# main_stack_dual_channel.net
KiCad netlist of a schematic drawn in Altium Designer
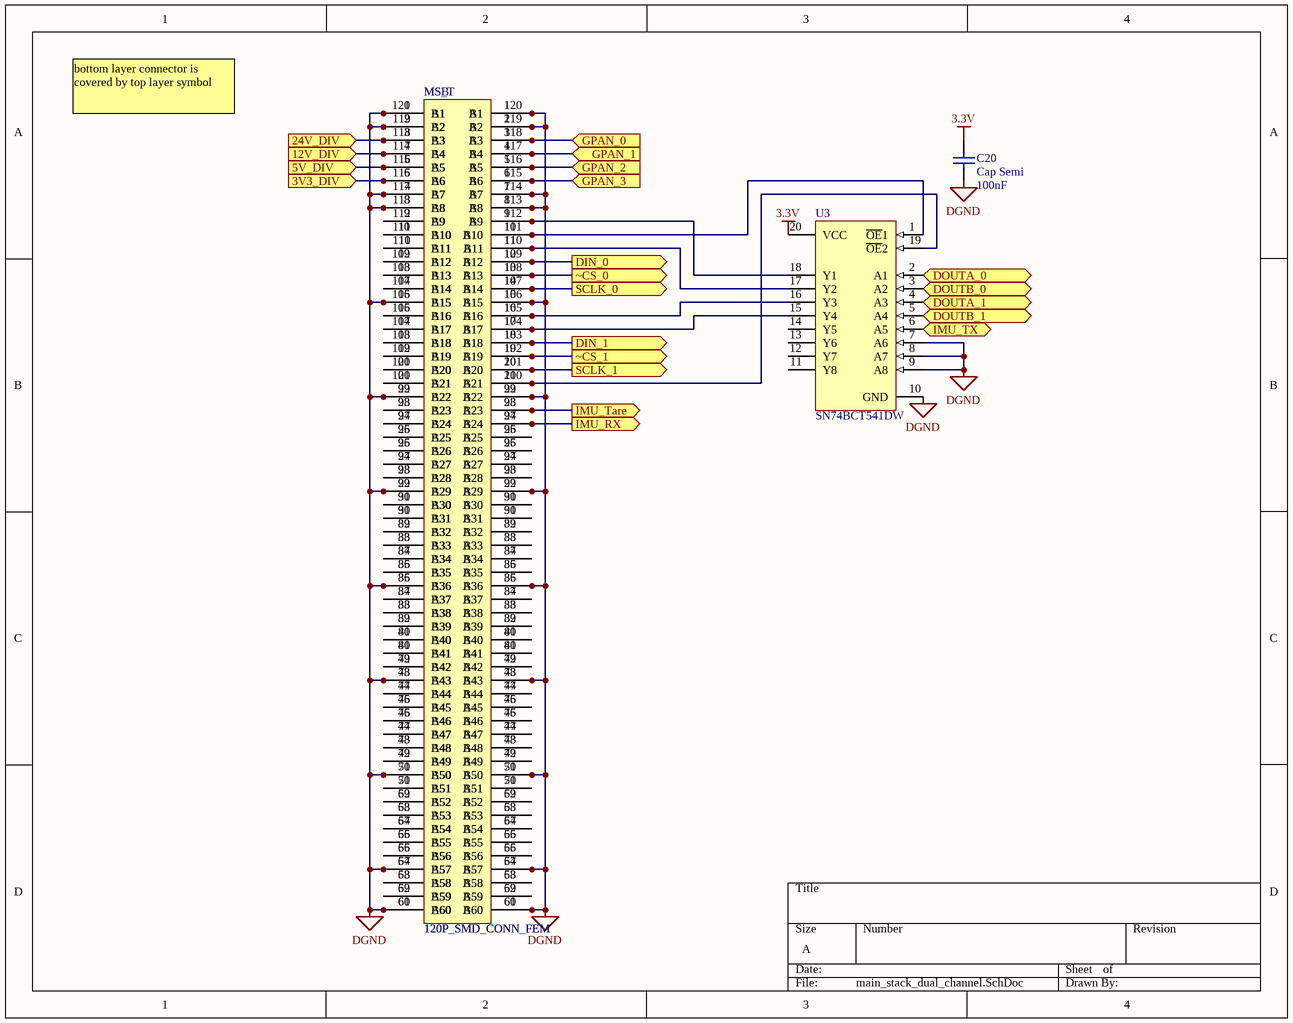
[diagram p0: main_stack_dual_channel.SchDoc]

(export (version "E")
  (design (tool "Eeschema 10.0.6"))
  (components
    (comp (ref "C20")
      (value "Cap Semi")
      (footprint "C0805")
      (description "Capacitor (Semiconductor SIM Model)")
      (fields (field (name "ALTIUM_VALUE") "100nF") (field (name "PUBLISHER") "Altium Limited"))
      (libsource (lib "Miscellaneous Devices") (part "Cap Semi"))
    )
    (comp (ref "MSB")
      (value "120P_SMD_CONN_FEM")
      (footprint "FX2-120P-1.27SV")
      (description "Main Stack Connector, Female")
      (fields (field (name "PART NUMBER") "FX2-120P-1.27SV(71)"))
      (libsource (lib "MDA_altium_common") (part "120P_SMD_CONN_FEM"))
    )
    (comp (ref "MS_T")
      (value "120P_SMD_CONN_FEM")
      (footprint "FX2-120P-1.27SV")
      (description "Main Stack Connector, Female")
      (fields (field (name "PART NUMBER") "FX2-120P-1.27SV(71)"))
      (libsource (lib "") (part "120P_SMD_CONN_FEM_1"))
    )
    (comp (ref "U3")
      (value "SN74BCT541DW")
      (footprint "TI Logic Buffer Line Driver:DW020")
      (description "Octal Buffer/Driver with 3-State Outputs")
      (fields (field (name "PUBLISHER") "Altium Limited"))
      (libsource (lib "TI Logic Buffer Line Driver") (part "SN74BCT541DW"))
    )
  )
  (nets
    (net (code "1") (name "/3V3_DIV") (class "Default")
      (node (ref "MSB") (pin "115") (pinfunction "B6_115") (pintype "passive"))
      (node (ref "MS_T") (pin "6") (pinfunction "A6_6") (pintype "passive"))
    )
    (net (code "2") (name "/5V_DIV") (class "Default")
      (node (ref "MSB") (pin "116") (pinfunction "B5_116") (pintype "passive"))
      (node (ref "MS_T") (pin "5") (pinfunction "A5_5") (pintype "passive"))
    )
    (net (code "3") (name "/12V_DIV") (class "Default")
      (node (ref "MSB") (pin "117") (pinfunction "B4_117") (pintype "passive"))
      (node (ref "MS_T") (pin "4") (pinfunction "A4_4") (pintype "passive"))
    )
    (net (code "4") (name "/24V_DIV") (class "Default")
      (node (ref "MSB") (pin "118") (pinfunction "B3_118") (pintype "passive"))
      (node (ref "MS_T") (pin "3") (pinfunction "A3_3") (pintype "passive"))
    )
    (net (code "5") (name "/DIN_0") (class "Default")
      (node (ref "MSB") (pin "12") (pinfunction "A12_12") (pintype "passive"))
      (node (ref "MS_T") (pin "109") (pinfunction "B12_109") (pintype "passive"))
    )
    (net (code "6") (name "/DIN_1") (class "Default")
      (node (ref "MSB") (pin "18") (pinfunction "A18_18") (pintype "passive"))
      (node (ref "MS_T") (pin "103") (pinfunction "B18_103") (pintype "passive"))
    )
    (net (code "7") (name "/DOUTA_0") (class "Default")
      (node (ref "U3") (pin "2") (pinfunction "A1_2") (pintype "input"))
    )
    (net (code "8") (name "/DOUTA_1") (class "Default")
      (node (ref "U3") (pin "4") (pinfunction "A3_4") (pintype "input"))
    )
    (net (code "9") (name "/DOUTB_0") (class "Default")
      (node (ref "U3") (pin "3") (pinfunction "A2_3") (pintype "input"))
    )
    (net (code "10") (name "/DOUTB_1") (class "Default")
      (node (ref "U3") (pin "5") (pinfunction "A4_5") (pintype "input"))
    )
    (net (code "11") (name "/GPAN_0") (class "Default")
      (node (ref "MSB") (pin "3") (pinfunction "A3_3") (pintype "passive"))
      (node (ref "MS_T") (pin "118") (pinfunction "B3_118") (pintype "passive"))
    )
    (net (code "12") (name "/GPAN_1") (class "Default")
      (node (ref "MSB") (pin "4") (pinfunction "A4_4") (pintype "passive"))
      (node (ref "MS_T") (pin "117") (pinfunction "B4_117") (pintype "passive"))
    )
    (net (code "13") (name "/GPAN_2") (class "Default")
      (node (ref "MSB") (pin "5") (pinfunction "A5_5") (pintype "passive"))
      (node (ref "MS_T") (pin "116") (pinfunction "B5_116") (pintype "passive"))
    )
    (net (code "14") (name "/GPAN_3") (class "Default")
      (node (ref "MSB") (pin "6") (pinfunction "A6_6") (pintype "passive"))
      (node (ref "MS_T") (pin "115") (pinfunction "B6_115") (pintype "passive"))
    )
    (net (code "15") (name "/IMU_RX") (class "Default")
      (node (ref "MSB") (pin "24") (pinfunction "A24_24") (pintype "passive"))
      (node (ref "MS_T") (pin "97") (pinfunction "B24_97") (pintype "passive"))
    )
    (net (code "16") (name "/IMU_TX") (class "Default")
      (node (ref "U3") (pin "6") (pinfunction "A5_6") (pintype "input"))
    )
    (net (code "17") (name "/IMU_Tare") (class "Default")
      (node (ref "MSB") (pin "23") (pinfunction "A23_23") (pintype "passive"))
      (node (ref "MS_T") (pin "98") (pinfunction "B23_98") (pintype "passive"))
    )
    (net (code "18") (name "/SCLK_0") (class "Default")
      (node (ref "MSB") (pin "14") (pinfunction "A14_14") (pintype "passive"))
      (node (ref "MS_T") (pin "107") (pinfunction "B14_107") (pintype "passive"))
    )
    (net (code "19") (name "/SCLK_1") (class "Default")
      (node (ref "MSB") (pin "20") (pinfunction "A20_20") (pintype "passive"))
      (node (ref "MS_T") (pin "101") (pinfunction "B20_101") (pintype "passive"))
    )
    (net (code "20") (name "/~CS_0") (class "Default")
      (node (ref "MSB") (pin "13") (pinfunction "A13_13") (pintype "passive"))
      (node (ref "MS_T") (pin "108") (pinfunction "B13_108") (pintype "passive"))
    )
    (net (code "21") (name "/~CS_1") (class "Default")
      (node (ref "MSB") (pin "19") (pinfunction "A19_19") (pintype "passive"))
      (node (ref "MS_T") (pin "102") (pinfunction "B19_102") (pintype "passive"))
    )
    (net (code "22") (name "3.3V") (class "Default")
      (node (ref "C20") (pin "2") (pinfunction "2_2") (pintype "passive"))
      (node (ref "U3") (pin "20") (pinfunction "VCC_20") (pintype "power_in"))
    )
    (net (code "23") (name "DGND") (class "Default")
      (node (ref "C20") (pin "1") (pinfunction "1_1") (pintype "passive"))
      (node (ref "MSB") (pin "1") (pinfunction "A1_1") (pintype "passive"))
      (node (ref "MSB") (pin "106") (pinfunction "B15_106") (pintype "passive"))
      (node (ref "MSB") (pin "113") (pinfunction "B8_113") (pintype "passive"))
      (node (ref "MSB") (pin "114") (pinfunction "B7_114") (pintype "passive"))
      (node (ref "MSB") (pin "119") (pinfunction "B2_119") (pintype "passive"))
      (node (ref "MSB") (pin "120") (pinfunction "B1_120") (pintype "passive"))
      (node (ref "MSB") (pin "15") (pinfunction "A15_15") (pintype "passive"))
      (node (ref "MSB") (pin "2") (pinfunction "A2_2") (pintype "passive"))
      (node (ref "MSB") (pin "22") (pinfunction "A22_22") (pintype "passive"))
      (node (ref "MSB") (pin "29") (pinfunction "A29_29") (pintype "passive"))
      (node (ref "MSB") (pin "36") (pinfunction "A36_36") (pintype "passive"))
      (node (ref "MSB") (pin "43") (pinfunction "A43_43") (pintype "passive"))
      (node (ref "MSB") (pin "50") (pinfunction "A50_50") (pintype "passive"))
      (node (ref "MSB") (pin "57") (pinfunction "A57_57") (pintype "passive"))
      (node (ref "MSB") (pin "60") (pinfunction "A60_60") (pintype "passive"))
      (node (ref "MSB") (pin "61") (pinfunction "B60_61") (pintype "passive"))
      (node (ref "MSB") (pin "64") (pinfunction "B57_64") (pintype "passive"))
      (node (ref "MSB") (pin "7") (pinfunction "A7_7") (pintype "passive"))
      (node (ref "MSB") (pin "71") (pinfunction "B50_71") (pintype "passive"))
      (node (ref "MSB") (pin "78") (pinfunction "B43_78") (pintype "passive"))
      (node (ref "MSB") (pin "8") (pinfunction "A8_8") (pintype "passive"))
      (node (ref "MSB") (pin "85") (pinfunction "B36_85") (pintype "passive"))
      (node (ref "MSB") (pin "92") (pinfunction "B29_92") (pintype "passive"))
      (node (ref "MSB") (pin "99") (pinfunction "B22_99") (pintype "passive"))
      (node (ref "MS_T") (pin "1") (pinfunction "A1_1") (pintype "passive"))
      (node (ref "MS_T") (pin "106") (pinfunction "B15_106") (pintype "passive"))
      (node (ref "MS_T") (pin "113") (pinfunction "B8_113") (pintype "passive"))
      (node (ref "MS_T") (pin "114") (pinfunction "B7_114") (pintype "passive"))
      (node (ref "MS_T") (pin "119") (pinfunction "B2_119") (pintype "passive"))
      (node (ref "MS_T") (pin "120") (pinfunction "B1_120") (pintype "passive"))
      (node (ref "MS_T") (pin "15") (pinfunction "A15_15") (pintype "passive"))
      (node (ref "MS_T") (pin "2") (pinfunction "A2_2") (pintype "passive"))
      (node (ref "MS_T") (pin "22") (pinfunction "A22_22") (pintype "passive"))
      (node (ref "MS_T") (pin "29") (pinfunction "A29_29") (pintype "passive"))
      (node (ref "MS_T") (pin "36") (pinfunction "A36_36") (pintype "passive"))
      (node (ref "MS_T") (pin "43") (pinfunction "A43_43") (pintype "passive"))
      (node (ref "MS_T") (pin "50") (pinfunction "A50_50") (pintype "passive"))
      (node (ref "MS_T") (pin "57") (pinfunction "A57_57") (pintype "passive"))
      (node (ref "MS_T") (pin "60") (pinfunction "A60_60") (pintype "passive"))
      (node (ref "MS_T") (pin "61") (pinfunction "B60_61") (pintype "passive"))
      (node (ref "MS_T") (pin "64") (pinfunction "B57_64") (pintype "passive"))
      (node (ref "MS_T") (pin "7") (pinfunction "A7_7") (pintype "passive"))
      (node (ref "MS_T") (pin "71") (pinfunction "B50_71") (pintype "passive"))
      (node (ref "MS_T") (pin "78") (pinfunction "B43_78") (pintype "passive"))
      (node (ref "MS_T") (pin "8") (pinfunction "A8_8") (pintype "passive"))
      (node (ref "MS_T") (pin "85") (pinfunction "B36_85") (pintype "passive"))
      (node (ref "MS_T") (pin "92") (pinfunction "B29_92") (pintype "passive"))
      (node (ref "MS_T") (pin "99") (pinfunction "B22_99") (pintype "passive"))
      (node (ref "U3") (pin "10") (pinfunction "GND_10") (pintype "power_in"))
      (node (ref "U3") (pin "7") (pinfunction "A6_7") (pintype "input"))
      (node (ref "U3") (pin "8") (pinfunction "A7_8") (pintype "input"))
      (node (ref "U3") (pin "9") (pinfunction "A8_9") (pintype "input"))
    )
    (net (code "24") (name "Net-(MSB-A9)") (class "Default")
      (node (ref "MSB") (pin "9") (pinfunction "A9_9") (pintype "passive"))
      (node (ref "MS_T") (pin "112") (pinfunction "B9_112") (pintype "passive"))
      (node (ref "U3") (pin "18") (pinfunction "Y1_18") (pintype "tri_state"))
    )
    (net (code "25") (name "Net-(MSB-A10)") (class "Default")
      (node (ref "MSB") (pin "10") (pinfunction "A10_10") (pintype "passive"))
      (node (ref "MS_T") (pin "111") (pinfunction "B10_111") (pintype "passive"))
      (node (ref "U3") (pin "1") (pinfunction "~{OE}1_1") (pintype "input"))
    )
    (net (code "26") (name "Net-(MSB-A11)") (class "Default")
      (node (ref "MSB") (pin "11") (pinfunction "A11_11") (pintype "passive"))
      (node (ref "MS_T") (pin "110") (pinfunction "B11_110") (pintype "passive"))
      (node (ref "U3") (pin "17") (pinfunction "Y2_17") (pintype "tri_state"))
    )
    (net (code "27") (name "Net-(MSB-A16)") (class "Default")
      (node (ref "MSB") (pin "16") (pinfunction "A16_16") (pintype "passive"))
      (node (ref "MS_T") (pin "105") (pinfunction "B16_105") (pintype "passive"))
      (node (ref "U3") (pin "16") (pinfunction "Y3_16") (pintype "tri_state"))
    )
    (net (code "28") (name "Net-(MSB-A17)") (class "Default")
      (node (ref "MSB") (pin "17") (pinfunction "A17_17") (pintype "passive"))
      (node (ref "MS_T") (pin "104") (pinfunction "B17_104") (pintype "passive"))
      (node (ref "U3") (pin "15") (pinfunction "Y4_15") (pintype "tri_state"))
    )
    (net (code "29") (name "Net-(MSB-A21)") (class "Default")
      (node (ref "MSB") (pin "21") (pinfunction "A21_21") (pintype "passive"))
      (node (ref "MS_T") (pin "100") (pinfunction "B21_100") (pintype "passive"))
      (node (ref "U3") (pin "19") (pinfunction "~{OE}2_19") (pintype "input"))
    )
    (net (code "30") (name "Net-(MSB-A25)") (class "Default")
      (node (ref "MSB") (pin "25") (pinfunction "A25_25") (pintype "passive"))
      (node (ref "MS_T") (pin "96") (pinfunction "B25_96") (pintype "passive"))
    )
    (net (code "31") (name "Net-(MSB-A26)") (class "Default")
      (node (ref "MSB") (pin "26") (pinfunction "A26_26") (pintype "passive"))
      (node (ref "MS_T") (pin "95") (pinfunction "B26_95") (pintype "passive"))
    )
    (net (code "32") (name "Net-(MSB-A27)") (class "Default")
      (node (ref "MSB") (pin "27") (pinfunction "A27_27") (pintype "passive"))
      (node (ref "MS_T") (pin "94") (pinfunction "B27_94") (pintype "passive"))
    )
    (net (code "33") (name "Net-(MSB-A28)") (class "Default")
      (node (ref "MSB") (pin "28") (pinfunction "A28_28") (pintype "passive"))
      (node (ref "MS_T") (pin "93") (pinfunction "B28_93") (pintype "passive"))
    )
    (net (code "34") (name "Net-(MSB-A30)") (class "Default")
      (node (ref "MSB") (pin "30") (pinfunction "A30_30") (pintype "passive"))
      (node (ref "MS_T") (pin "91") (pinfunction "B30_91") (pintype "passive"))
    )
    (net (code "35") (name "Net-(MSB-A31)") (class "Default")
      (node (ref "MSB") (pin "31") (pinfunction "A31_31") (pintype "passive"))
      (node (ref "MS_T") (pin "90") (pinfunction "B31_90") (pintype "passive"))
    )
    (net (code "36") (name "Net-(MSB-A32)") (class "Default")
      (node (ref "MSB") (pin "32") (pinfunction "A32_32") (pintype "passive"))
      (node (ref "MS_T") (pin "89") (pinfunction "B32_89") (pintype "passive"))
    )
    (net (code "37") (name "Net-(MSB-A33)") (class "Default")
      (node (ref "MSB") (pin "33") (pinfunction "A33_33") (pintype "passive"))
      (node (ref "MS_T") (pin "88") (pinfunction "B33_88") (pintype "passive"))
    )
    (net (code "38") (name "Net-(MSB-A34)") (class "Default")
      (node (ref "MSB") (pin "34") (pinfunction "A34_34") (pintype "passive"))
      (node (ref "MS_T") (pin "87") (pinfunction "B34_87") (pintype "passive"))
    )
    (net (code "39") (name "Net-(MSB-A35)") (class "Default")
      (node (ref "MSB") (pin "35") (pinfunction "A35_35") (pintype "passive"))
      (node (ref "MS_T") (pin "86") (pinfunction "B35_86") (pintype "passive"))
    )
    (net (code "40") (name "Net-(MSB-A37)") (class "Default")
      (node (ref "MSB") (pin "37") (pinfunction "A37_37") (pintype "passive"))
      (node (ref "MS_T") (pin "84") (pinfunction "B37_84") (pintype "passive"))
    )
    (net (code "41") (name "Net-(MSB-A38)") (class "Default")
      (node (ref "MSB") (pin "38") (pinfunction "A38_38") (pintype "passive"))
      (node (ref "MS_T") (pin "83") (pinfunction "B38_83") (pintype "passive"))
    )
    (net (code "42") (name "Net-(MSB-A39)") (class "Default")
      (node (ref "MSB") (pin "39") (pinfunction "A39_39") (pintype "passive"))
      (node (ref "MS_T") (pin "82") (pinfunction "B39_82") (pintype "passive"))
    )
    (net (code "43") (name "Net-(MSB-A40)") (class "Default")
      (node (ref "MSB") (pin "40") (pinfunction "A40_40") (pintype "passive"))
      (node (ref "MS_T") (pin "81") (pinfunction "B40_81") (pintype "passive"))
    )
    (net (code "44") (name "Net-(MSB-A41)") (class "Default")
      (node (ref "MSB") (pin "41") (pinfunction "A41_41") (pintype "passive"))
      (node (ref "MS_T") (pin "80") (pinfunction "B41_80") (pintype "passive"))
    )
    (net (code "45") (name "Net-(MSB-A42)") (class "Default")
      (node (ref "MSB") (pin "42") (pinfunction "A42_42") (pintype "passive"))
      (node (ref "MS_T") (pin "79") (pinfunction "B42_79") (pintype "passive"))
    )
    (net (code "46") (name "Net-(MSB-A44)") (class "Default")
      (node (ref "MSB") (pin "44") (pinfunction "A44_44") (pintype "passive"))
      (node (ref "MS_T") (pin "77") (pinfunction "B44_77") (pintype "passive"))
    )
    (net (code "47") (name "Net-(MSB-A45)") (class "Default")
      (node (ref "MSB") (pin "45") (pinfunction "A45_45") (pintype "passive"))
      (node (ref "MS_T") (pin "76") (pinfunction "B45_76") (pintype "passive"))
    )
    (net (code "48") (name "Net-(MSB-A46)") (class "Default")
      (node (ref "MSB") (pin "46") (pinfunction "A46_46") (pintype "passive"))
      (node (ref "MS_T") (pin "75") (pinfunction "B46_75") (pintype "passive"))
    )
    (net (code "49") (name "Net-(MSB-A47)") (class "Default")
      (node (ref "MSB") (pin "47") (pinfunction "A47_47") (pintype "passive"))
      (node (ref "MS_T") (pin "74") (pinfunction "B47_74") (pintype "passive"))
    )
    (net (code "50") (name "Net-(MSB-A48)") (class "Default")
      (node (ref "MSB") (pin "48") (pinfunction "A48_48") (pintype "passive"))
      (node (ref "MS_T") (pin "73") (pinfunction "B48_73") (pintype "passive"))
    )
    (net (code "51") (name "Net-(MSB-A49)") (class "Default")
      (node (ref "MSB") (pin "49") (pinfunction "A49_49") (pintype "passive"))
      (node (ref "MS_T") (pin "72") (pinfunction "B49_72") (pintype "passive"))
    )
    (net (code "52") (name "Net-(MSB-A51)") (class "Default")
      (node (ref "MSB") (pin "51") (pinfunction "A51_51") (pintype "passive"))
      (node (ref "MS_T") (pin "70") (pinfunction "B51_70") (pintype "passive"))
    )
    (net (code "53") (name "Net-(MSB-A52)") (class "Default")
      (node (ref "MSB") (pin "52") (pinfunction "A52_52") (pintype "passive"))
      (node (ref "MS_T") (pin "69") (pinfunction "B52_69") (pintype "passive"))
    )
    (net (code "54") (name "Net-(MSB-A53)") (class "Default")
      (node (ref "MSB") (pin "53") (pinfunction "A53_53") (pintype "passive"))
      (node (ref "MS_T") (pin "68") (pinfunction "B53_68") (pintype "passive"))
    )
    (net (code "55") (name "Net-(MSB-A54)") (class "Default")
      (node (ref "MSB") (pin "54") (pinfunction "A54_54") (pintype "passive"))
      (node (ref "MS_T") (pin "67") (pinfunction "B54_67") (pintype "passive"))
    )
    (net (code "56") (name "Net-(MSB-A55)") (class "Default")
      (node (ref "MSB") (pin "55") (pinfunction "A55_55") (pintype "passive"))
      (node (ref "MS_T") (pin "66") (pinfunction "B55_66") (pintype "passive"))
    )
    (net (code "57") (name "Net-(MSB-A56)") (class "Default")
      (node (ref "MSB") (pin "56") (pinfunction "A56_56") (pintype "passive"))
      (node (ref "MS_T") (pin "65") (pinfunction "B56_65") (pintype "passive"))
    )
    (net (code "58") (name "Net-(MSB-A58)") (class "Default")
      (node (ref "MSB") (pin "58") (pinfunction "A58_58") (pintype "passive"))
      (node (ref "MS_T") (pin "63") (pinfunction "B58_63") (pintype "passive"))
    )
    (net (code "59") (name "Net-(MSB-A59)") (class "Default")
      (node (ref "MSB") (pin "59") (pinfunction "A59_59") (pintype "passive"))
      (node (ref "MS_T") (pin "62") (pinfunction "B59_62") (pintype "passive"))
    )
    (net (code "60") (name "Net-(MSB-B9)") (class "Default")
      (node (ref "MSB") (pin "112") (pinfunction "B9_112") (pintype "passive"))
      (node (ref "MS_T") (pin "9") (pinfunction "A9_9") (pintype "passive"))
    )
    (net (code "61") (name "Net-(MSB-B10)") (class "Default")
      (node (ref "MSB") (pin "111") (pinfunction "B10_111") (pintype "passive"))
      (node (ref "MS_T") (pin "10") (pinfunction "A10_10") (pintype "passive"))
    )
    (net (code "62") (name "Net-(MSB-B11)") (class "Default")
      (node (ref "MSB") (pin "110") (pinfunction "B11_110") (pintype "passive"))
      (node (ref "MS_T") (pin "11") (pinfunction "A11_11") (pintype "passive"))
    )
    (net (code "63") (name "Net-(MSB-B12)") (class "Default")
      (node (ref "MSB") (pin "109") (pinfunction "B12_109") (pintype "passive"))
      (node (ref "MS_T") (pin "12") (pinfunction "A12_12") (pintype "passive"))
    )
    (net (code "64") (name "Net-(MSB-B13)") (class "Default")
      (node (ref "MSB") (pin "108") (pinfunction "B13_108") (pintype "passive"))
      (node (ref "MS_T") (pin "13") (pinfunction "A13_13") (pintype "passive"))
    )
    (net (code "65") (name "Net-(MSB-B14)") (class "Default")
      (node (ref "MSB") (pin "107") (pinfunction "B14_107") (pintype "passive"))
      (node (ref "MS_T") (pin "14") (pinfunction "A14_14") (pintype "passive"))
    )
    (net (code "66") (name "Net-(MSB-B16)") (class "Default")
      (node (ref "MSB") (pin "105") (pinfunction "B16_105") (pintype "passive"))
      (node (ref "MS_T") (pin "16") (pinfunction "A16_16") (pintype "passive"))
    )
    (net (code "67") (name "Net-(MSB-B17)") (class "Default")
      (node (ref "MSB") (pin "104") (pinfunction "B17_104") (pintype "passive"))
      (node (ref "MS_T") (pin "17") (pinfunction "A17_17") (pintype "passive"))
    )
    (net (code "68") (name "Net-(MSB-B18)") (class "Default")
      (node (ref "MSB") (pin "103") (pinfunction "B18_103") (pintype "passive"))
      (node (ref "MS_T") (pin "18") (pinfunction "A18_18") (pintype "passive"))
    )
    (net (code "69") (name "Net-(MSB-B19)") (class "Default")
      (node (ref "MSB") (pin "102") (pinfunction "B19_102") (pintype "passive"))
      (node (ref "MS_T") (pin "19") (pinfunction "A19_19") (pintype "passive"))
    )
    (net (code "70") (name "Net-(MSB-B20)") (class "Default")
      (node (ref "MSB") (pin "101") (pinfunction "B20_101") (pintype "passive"))
      (node (ref "MS_T") (pin "20") (pinfunction "A20_20") (pintype "passive"))
    )
    (net (code "71") (name "Net-(MSB-B21)") (class "Default")
      (node (ref "MSB") (pin "100") (pinfunction "B21_100") (pintype "passive"))
      (node (ref "MS_T") (pin "21") (pinfunction "A21_21") (pintype "passive"))
    )
    (net (code "72") (name "Net-(MSB-B23)") (class "Default")
      (node (ref "MSB") (pin "98") (pinfunction "B23_98") (pintype "passive"))
      (node (ref "MS_T") (pin "23") (pinfunction "A23_23") (pintype "passive"))
    )
    (net (code "73") (name "Net-(MSB-B24)") (class "Default")
      (node (ref "MSB") (pin "97") (pinfunction "B24_97") (pintype "passive"))
      (node (ref "MS_T") (pin "24") (pinfunction "A24_24") (pintype "passive"))
    )
    (net (code "74") (name "Net-(MSB-B25)") (class "Default")
      (node (ref "MSB") (pin "96") (pinfunction "B25_96") (pintype "passive"))
      (node (ref "MS_T") (pin "25") (pinfunction "A25_25") (pintype "passive"))
    )
    (net (code "75") (name "Net-(MSB-B26)") (class "Default")
      (node (ref "MSB") (pin "95") (pinfunction "B26_95") (pintype "passive"))
      (node (ref "MS_T") (pin "26") (pinfunction "A26_26") (pintype "passive"))
    )
    (net (code "76") (name "Net-(MSB-B27)") (class "Default")
      (node (ref "MSB") (pin "94") (pinfunction "B27_94") (pintype "passive"))
      (node (ref "MS_T") (pin "27") (pinfunction "A27_27") (pintype "passive"))
    )
    (net (code "77") (name "Net-(MSB-B28)") (class "Default")
      (node (ref "MSB") (pin "93") (pinfunction "B28_93") (pintype "passive"))
      (node (ref "MS_T") (pin "28") (pinfunction "A28_28") (pintype "passive"))
    )
    (net (code "78") (name "Net-(MSB-B30)") (class "Default")
      (node (ref "MSB") (pin "91") (pinfunction "B30_91") (pintype "passive"))
      (node (ref "MS_T") (pin "30") (pinfunction "A30_30") (pintype "passive"))
    )
    (net (code "79") (name "Net-(MSB-B31)") (class "Default")
      (node (ref "MSB") (pin "90") (pinfunction "B31_90") (pintype "passive"))
      (node (ref "MS_T") (pin "31") (pinfunction "A31_31") (pintype "passive"))
    )
    (net (code "80") (name "Net-(MSB-B32)") (class "Default")
      (node (ref "MSB") (pin "89") (pinfunction "B32_89") (pintype "passive"))
      (node (ref "MS_T") (pin "32") (pinfunction "A32_32") (pintype "passive"))
    )
    (net (code "81") (name "Net-(MSB-B33)") (class "Default")
      (node (ref "MSB") (pin "88") (pinfunction "B33_88") (pintype "passive"))
      (node (ref "MS_T") (pin "33") (pinfunction "A33_33") (pintype "passive"))
    )
    (net (code "82") (name "Net-(MSB-B34)") (class "Default")
      (node (ref "MSB") (pin "87") (pinfunction "B34_87") (pintype "passive"))
      (node (ref "MS_T") (pin "34") (pinfunction "A34_34") (pintype "passive"))
    )
    (net (code "83") (name "Net-(MSB-B35)") (class "Default")
      (node (ref "MSB") (pin "86") (pinfunction "B35_86") (pintype "passive"))
      (node (ref "MS_T") (pin "35") (pinfunction "A35_35") (pintype "passive"))
    )
    (net (code "84") (name "Net-(MSB-B37)") (class "Default")
      (node (ref "MSB") (pin "84") (pinfunction "B37_84") (pintype "passive"))
      (node (ref "MS_T") (pin "37") (pinfunction "A37_37") (pintype "passive"))
    )
    (net (code "85") (name "Net-(MSB-B38)") (class "Default")
      (node (ref "MSB") (pin "83") (pinfunction "B38_83") (pintype "passive"))
      (node (ref "MS_T") (pin "38") (pinfunction "A38_38") (pintype "passive"))
    )
    (net (code "86") (name "Net-(MSB-B39)") (class "Default")
      (node (ref "MSB") (pin "82") (pinfunction "B39_82") (pintype "passive"))
      (node (ref "MS_T") (pin "39") (pinfunction "A39_39") (pintype "passive"))
    )
    (net (code "87") (name "Net-(MSB-B40)") (class "Default")
      (node (ref "MSB") (pin "81") (pinfunction "B40_81") (pintype "passive"))
      (node (ref "MS_T") (pin "40") (pinfunction "A40_40") (pintype "passive"))
    )
    (net (code "88") (name "Net-(MSB-B41)") (class "Default")
      (node (ref "MSB") (pin "80") (pinfunction "B41_80") (pintype "passive"))
      (node (ref "MS_T") (pin "41") (pinfunction "A41_41") (pintype "passive"))
    )
    (net (code "89") (name "Net-(MSB-B42)") (class "Default")
      (node (ref "MSB") (pin "79") (pinfunction "B42_79") (pintype "passive"))
      (node (ref "MS_T") (pin "42") (pinfunction "A42_42") (pintype "passive"))
    )
    (net (code "90") (name "Net-(MSB-B44)") (class "Default")
      (node (ref "MSB") (pin "77") (pinfunction "B44_77") (pintype "passive"))
      (node (ref "MS_T") (pin "44") (pinfunction "A44_44") (pintype "passive"))
    )
    (net (code "91") (name "Net-(MSB-B45)") (class "Default")
      (node (ref "MSB") (pin "76") (pinfunction "B45_76") (pintype "passive"))
      (node (ref "MS_T") (pin "45") (pinfunction "A45_45") (pintype "passive"))
    )
    (net (code "92") (name "Net-(MSB-B46)") (class "Default")
      (node (ref "MSB") (pin "75") (pinfunction "B46_75") (pintype "passive"))
      (node (ref "MS_T") (pin "46") (pinfunction "A46_46") (pintype "passive"))
    )
    (net (code "93") (name "Net-(MSB-B47)") (class "Default")
      (node (ref "MSB") (pin "74") (pinfunction "B47_74") (pintype "passive"))
      (node (ref "MS_T") (pin "47") (pinfunction "A47_47") (pintype "passive"))
    )
    (net (code "94") (name "Net-(MSB-B48)") (class "Default")
      (node (ref "MSB") (pin "73") (pinfunction "B48_73") (pintype "passive"))
      (node (ref "MS_T") (pin "48") (pinfunction "A48_48") (pintype "passive"))
    )
    (net (code "95") (name "Net-(MSB-B49)") (class "Default")
      (node (ref "MSB") (pin "72") (pinfunction "B49_72") (pintype "passive"))
      (node (ref "MS_T") (pin "49") (pinfunction "A49_49") (pintype "passive"))
    )
    (net (code "96") (name "Net-(MSB-B51)") (class "Default")
      (node (ref "MSB") (pin "70") (pinfunction "B51_70") (pintype "passive"))
      (node (ref "MS_T") (pin "51") (pinfunction "A51_51") (pintype "passive"))
    )
    (net (code "97") (name "Net-(MSB-B52)") (class "Default")
      (node (ref "MSB") (pin "69") (pinfunction "B52_69") (pintype "passive"))
      (node (ref "MS_T") (pin "52") (pinfunction "A52_52") (pintype "passive"))
    )
    (net (code "98") (name "Net-(MSB-B53)") (class "Default")
      (node (ref "MSB") (pin "68") (pinfunction "B53_68") (pintype "passive"))
      (node (ref "MS_T") (pin "53") (pinfunction "A53_53") (pintype "passive"))
    )
    (net (code "99") (name "Net-(MSB-B54)") (class "Default")
      (node (ref "MSB") (pin "67") (pinfunction "B54_67") (pintype "passive"))
      (node (ref "MS_T") (pin "54") (pinfunction "A54_54") (pintype "passive"))
    )
    (net (code "100") (name "Net-(MSB-B55)") (class "Default")
      (node (ref "MSB") (pin "66") (pinfunction "B55_66") (pintype "passive"))
      (node (ref "MS_T") (pin "55") (pinfunction "A55_55") (pintype "passive"))
    )
    (net (code "101") (name "Net-(MSB-B56)") (class "Default")
      (node (ref "MSB") (pin "65") (pinfunction "B56_65") (pintype "passive"))
      (node (ref "MS_T") (pin "56") (pinfunction "A56_56") (pintype "passive"))
    )
    (net (code "102") (name "Net-(MSB-B58)") (class "Default")
      (node (ref "MSB") (pin "63") (pinfunction "B58_63") (pintype "passive"))
      (node (ref "MS_T") (pin "58") (pinfunction "A58_58") (pintype "passive"))
    )
    (net (code "103") (name "Net-(MSB-B59)") (class "Default")
      (node (ref "MSB") (pin "62") (pinfunction "B59_62") (pintype "passive"))
      (node (ref "MS_T") (pin "59") (pinfunction "A59_59") (pintype "passive"))
    )
    (net (code "104") (name "unconnected-(U3-Y5-Pad14)") (class "Default")
      (node (ref "U3") (pin "14") (pinfunction "Y5_14") (pintype "tri_state"))
    )
    (net (code "105") (name "unconnected-(U3-Y6-Pad13)") (class "Default")
      (node (ref "U3") (pin "13") (pinfunction "Y6_13") (pintype "tri_state"))
    )
    (net (code "106") (name "unconnected-(U3-Y7-Pad12)") (class "Default")
      (node (ref "U3") (pin "12") (pinfunction "Y7_12") (pintype "tri_state"))
    )
    (net (code "107") (name "unconnected-(U3-Y8-Pad11)") (class "Default")
      (node (ref "U3") (pin "11") (pinfunction "Y8_11") (pintype "tri_state"))
    )
  )
)
